# Sheet1.net
KiCad netlist of a schematic drawn in Altium Designer
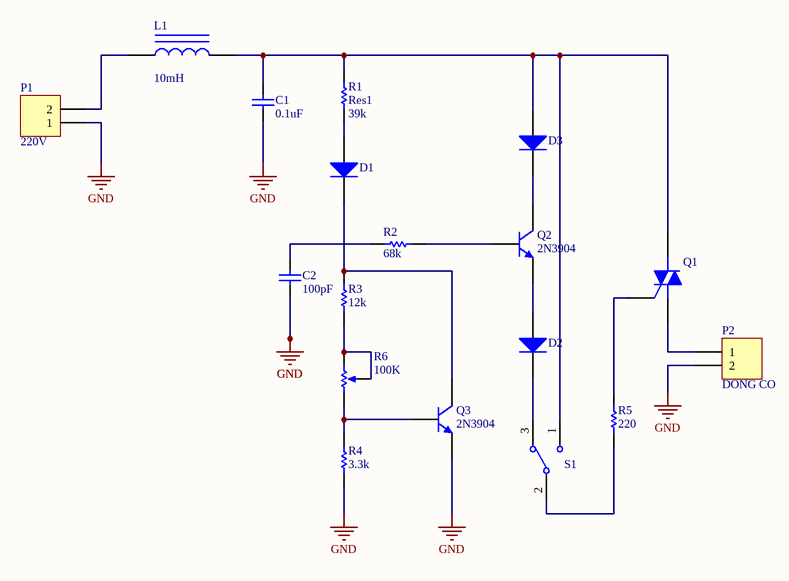
[diagram p0: Sheet1.SchDoc]

(export (version "E")
  (design (tool "Eeschema 10.0.6"))
  (components
    (comp (ref "C1")
      (value "0.1uF")
      (footprint "CAPR2.54-5.1x3.2")
      (description "Capacitor")
      (fields (field (name "Comment") "Cap") (field (name "PUBLISHER") "Altium Limited"))
      (libsource (lib "Miscellaneous Devices") (part "Cap"))
    )
    (comp (ref "C2")
      (value "100pF")
      (footprint "CAPR2.54-5.1x3.2")
      (description "Capacitor")
      (fields (field (name "Comment") "Cap") (field (name "PUBLISHER") "Altium Limited"))
      (libsource (lib "Miscellaneous Devices") (part "Cap"))
    )
    (comp (ref "D1")
      (value "Diode")
      (footprint "AXIAL-0.3")
      (description "Default Diode")
      (fields (field (name "PUBLISHER") "Altium Limited"))
      (libsource (lib "Miscellaneous Devices") (part "Diode"))
    )
    (comp (ref "D2")
      (value "Diode")
      (footprint "AXIAL-0.3")
      (description "Default Diode")
      (fields (field (name "PUBLISHER") "Altium Limited"))
      (libsource (lib "Miscellaneous Devices") (part "Diode"))
    )
    (comp (ref "D3")
      (value "Diode")
      (footprint "AXIAL-0.3")
      (description "Default Diode")
      (fields (field (name "PUBLISHER") "Altium Limited"))
      (libsource (lib "Miscellaneous Devices") (part "Diode"))
    )
    (comp (ref "L1")
      (value "10mH")
      (footprint "AXIAL-0.9")
      (description "Magnetic-Core Inductor")
      (fields (field (name "Comment") "Inductor Iron") (field (name "PUBLISHER") "Altium Limited"))
      (libsource (lib "Miscellaneous Devices") (part "Inductor Iron"))
    )
    (comp (ref "P1")
      (value "220V")
      (footprint "HDR1X2")
      (description "Header, 2-Pin")
      (fields (field (name "PUBLISHER") "Altium Limited"))
      (libsource (lib "Miscellaneous Connectors") (part "Header 2"))
    )
    (comp (ref "P2")
      (value "DONG CO")
      (footprint "HDR1X2")
      (description "Header, 2-Pin")
      (fields (field (name "PUBLISHER") "Altium Limited"))
      (libsource (lib "") (part "Header 2_1"))
    )
    (comp (ref "Q1")
      (value "Triac")
      (footprint "SFM-T3/A2.4V")
      (description "Silicon Bidirectional Triode Thyristor")
      (fields (field (name "PUBLISHER") "Altium Limited"))
      (libsource (lib "Miscellaneous Devices") (part "Triac"))
    )
    (comp (ref "Q2")
      (value "2N3904")
      (footprint "SFM-T3/X1.6V")
      (description "NPN General Purpose Amplifier")
      (fields (field (name "PUBLISHER") "Altium Limited"))
      (libsource (lib "Miscellaneous Devices") (part "2N3904"))
    )
    (comp (ref "Q3")
      (value "2N3904")
      (footprint "SFM-T3/X1.6V")
      (description "NPN General Purpose Amplifier")
      (fields (field (name "PUBLISHER") "Altium Limited"))
      (libsource (lib "Miscellaneous Devices") (part "2N3904"))
    )
    (comp (ref "R1")
      (value "Res1")
      (footprint "AXIAL-0.3")
      (description "Resistor")
      (fields (field (name "ALTIUM_VALUE") "39k") (field (name "PUBLISHER") "Altium Limited"))
      (libsource (lib "Miscellaneous Devices") (part "Res1"))
    )
    (comp (ref "R2")
      (value "68k")
      (footprint "AXIAL-0.3")
      (description "Resistor")
      (fields (field (name "Comment") "Res1") (field (name "PUBLISHER") "Altium Limited"))
      (libsource (lib "Miscellaneous Devices") (part "Res1"))
    )
    (comp (ref "R3")
      (value "12k")
      (footprint "AXIAL-0.3")
      (description "Resistor")
      (fields (field (name "Comment") "Res1") (field (name "PUBLISHER") "Altium Limited"))
      (libsource (lib "Miscellaneous Devices") (part "Res1"))
    )
    (comp (ref "R4")
      (value "3.3k")
      (footprint "AXIAL-0.3")
      (description "Resistor")
      (fields (field (name "Comment") "Res1") (field (name "PUBLISHER") "Altium Limited"))
      (libsource (lib "Miscellaneous Devices") (part "Res1"))
    )
    (comp (ref "R5")
      (value "220")
      (footprint "AXIAL-0.3")
      (description "Resistor")
      (fields (field (name "Comment") "Res1") (field (name "PUBLISHER") "Altium Limited"))
      (libsource (lib "Miscellaneous Devices") (part "Res1"))
    )
    (comp (ref "R6")
      (value "100K")
      (footprint "VR5")
      (description "Potentiometer")
      (fields (field (name "Comment") "RPot") (field (name "PUBLISHER") "Altium Limited"))
      (libsource (lib "Miscellaneous Devices") (part "RPot"))
    )
    (comp (ref "S1")
      (value "SW-SPDT")
      (footprint "TL36WW15050")
      (description "SPDT Subminiature Toggle Switch, Right Angle Mounting, Vertical Actuation")
      (fields (field (name "PUBLISHER") "Altium Limited"))
      (libsource (lib "Miscellaneous Devices") (part "SW-SPDT"))
    )
  )
  (nets
    (net (code "1") (name "GND") (class "Default")
      (node (ref "C1") (pin "1") (pinfunction "1_1") (pintype "passive"))
      (node (ref "C2") (pin "1") (pinfunction "1_1") (pintype "passive"))
      (node (ref "P1") (pin "1") (pinfunction "1_1") (pintype "passive"))
      (node (ref "P2") (pin "2") (pinfunction "2_2") (pintype "passive"))
      (node (ref "Q3") (pin "1") (pinfunction "E_1") (pintype "passive"))
      (node (ref "R4") (pin "1") (pinfunction "1_1") (pintype "passive"))
    )
    (net (code "2") (name "Net-(C2-Pad2)") (class "Default")
      (node (ref "C2") (pin "2") (pinfunction "2_2") (pintype "passive"))
      (node (ref "R2") (pin "1") (pinfunction "1_1") (pintype "passive"))
    )
    (net (code "3") (name "Net-(D1-A)") (class "Default")
      (node (ref "D1") (pin "1") (pinfunction "A_1") (pintype "passive"))
      (node (ref "R1") (pin "1") (pinfunction "1_1") (pintype "passive"))
    )
    (net (code "4") (name "Net-(D1-K)") (class "Default")
      (node (ref "D1") (pin "2") (pinfunction "K_2") (pintype "passive"))
      (node (ref "Q3") (pin "3") (pinfunction "C_3") (pintype "passive"))
      (node (ref "R3") (pin "2") (pinfunction "2_2") (pintype "passive"))
    )
    (net (code "5") (name "Net-(D2-A)") (class "Default")
      (node (ref "D2") (pin "1") (pinfunction "A_1") (pintype "passive"))
      (node (ref "Q2") (pin "1") (pinfunction "E_1") (pintype "passive"))
    )
    (net (code "6") (name "Net-(D2-K)") (class "Default")
      (node (ref "D2") (pin "2") (pinfunction "K_2") (pintype "passive"))
      (node (ref "S1") (pin "3") (pinfunction "3_3") (pintype "passive"))
    )
    (net (code "7") (name "Net-(D3-A)") (class "Default")
      (node (ref "C1") (pin "2") (pinfunction "2_2") (pintype "passive"))
      (node (ref "D3") (pin "1") (pinfunction "A_1") (pintype "passive"))
      (node (ref "L1") (pin "2") (pinfunction "2_2") (pintype "passive"))
      (node (ref "Q1") (pin "2") (pinfunction "M2_2") (pintype "passive"))
      (node (ref "R1") (pin "2") (pinfunction "2_2") (pintype "passive"))
      (node (ref "S1") (pin "1") (pinfunction "1_1") (pintype "passive"))
    )
    (net (code "8") (name "Net-(D3-K)") (class "Default")
      (node (ref "D3") (pin "2") (pinfunction "K_2") (pintype "passive"))
      (node (ref "Q2") (pin "3") (pinfunction "C_3") (pintype "passive"))
    )
    (net (code "9") (name "Net-(L1-Pad1)") (class "Default")
      (node (ref "L1") (pin "1") (pinfunction "1_1") (pintype "passive"))
      (node (ref "P1") (pin "2") (pinfunction "2_2") (pintype "passive"))
    )
    (net (code "10") (name "Net-(Q1-G)") (class "Default")
      (node (ref "Q1") (pin "3") (pinfunction "G_3") (pintype "passive"))
      (node (ref "R5") (pin "2") (pinfunction "2_2") (pintype "passive"))
    )
    (net (code "11") (name "Net-(Q1-M1)") (class "Default")
      (node (ref "P2") (pin "1") (pinfunction "1_1") (pintype "passive"))
      (node (ref "Q1") (pin "1") (pinfunction "M1_1") (pintype "passive"))
    )
    (net (code "12") (name "Net-(Q2-B)") (class "Default")
      (node (ref "Q2") (pin "2") (pinfunction "B_2") (pintype "passive"))
      (node (ref "R2") (pin "2") (pinfunction "2_2") (pintype "passive"))
    )
    (net (code "13") (name "Net-(Q3-B)") (class "Default")
      (node (ref "Q3") (pin "2") (pinfunction "B_2") (pintype "passive"))
      (node (ref "R4") (pin "2") (pinfunction "2_2") (pintype "passive"))
      (node (ref "R6") (pin "1") (pinfunction "TOP_1") (pintype "passive"))
    )
    (net (code "14") (name "Net-(R5-Pad1)") (class "Default")
      (node (ref "R5") (pin "1") (pinfunction "1_1") (pintype "passive"))
      (node (ref "S1") (pin "2") (pinfunction "2_2") (pintype "passive"))
    )
    (net (code "15") (name "Net-(R6-BOT)") (class "Default")
      (node (ref "R3") (pin "1") (pinfunction "1_1") (pintype "passive"))
      (node (ref "R6") (pin "2") (pinfunction "BOT_2") (pintype "passive"))
      (node (ref "R6") (pin "3") (pinfunction "TAP_3") (pintype "passive"))
    )
  )
)
